# PB_Conn.net
KiCad netlist of a schematic drawn in Altium Designer
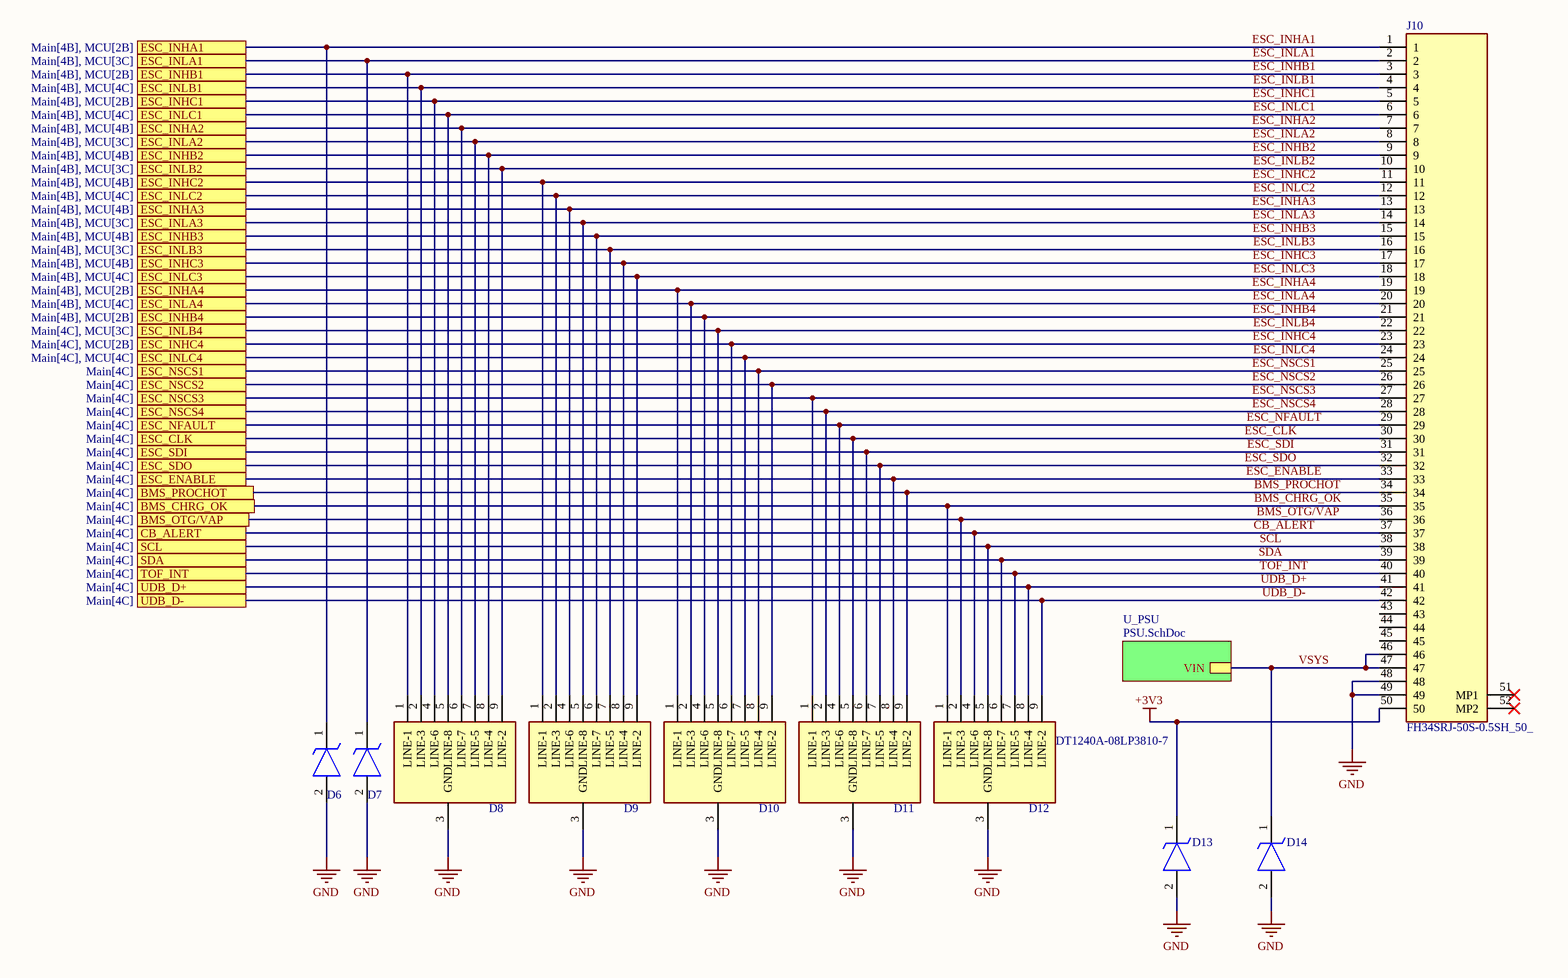
[diagram p0: PB_Conn.SchDoc]

(export (version "E")
  (design (tool "Eeschema 10.0.6"))
  (components
    (comp (ref "D6")
      (value "D1213A-01LP4-7B")
      (footprint "SamacSys:D1213A01LP47B")
      (description "TVS Diode (Uni-directional)")
      (fields (field (name "MOUSER PART NUMBER") "621-D1213A-01LP4-7B"))
      (libsource (lib "*") (part "D1213A-01LP4-7B"))
    )
    (comp (ref "D7")
      (value "D1213A-01LP4-7B")
      (footprint "SamacSys:D1213A01LP47B")
      (description "TVS Diode (Uni-directional)")
      (fields (field (name "MOUSER PART NUMBER") "621-D1213A-01LP4-7B"))
      (libsource (lib "*") (part "D1213A-01LP4-7B"))
    )
    (comp (ref "D8")
      (value "DT1240A-08LP3810-7")
      (footprint "SamacSys:DT1240A08LP38107")
      (description "TVS Diode (Uni-directional)")
      (fields (field (name "MOUSER PART NUMBER") "621-DT1240A08LP38107"))
      (libsource (lib "SamacSys") (part "DT1240A-08LP3810-7"))
    )
    (comp (ref "D9")
      (value "DT1240A-08LP3810-7")
      (footprint "SamacSys:DT1240A08LP38107")
      (description "TVS Diode (Uni-directional)")
      (fields (field (name "MOUSER PART NUMBER") "621-DT1240A08LP38107"))
      (libsource (lib "SamacSys") (part "DT1240A-08LP3810-7"))
    )
    (comp (ref "D10")
      (value "DT1240A-08LP3810-7")
      (footprint "SamacSys:DT1240A08LP38107")
      (description "TVS Diode (Uni-directional)")
      (fields (field (name "MOUSER PART NUMBER") "621-DT1240A08LP38107"))
      (libsource (lib "SamacSys") (part "DT1240A-08LP3810-7"))
    )
    (comp (ref "D11")
      (value "DT1240A-08LP3810-7")
      (footprint "SamacSys:DT1240A08LP38107")
      (description "TVS Diode (Uni-directional)")
      (fields (field (name "MOUSER PART NUMBER") "621-DT1240A08LP38107"))
      (libsource (lib "SamacSys") (part "DT1240A-08LP3810-7"))
    )
    (comp (ref "D12")
      (value "DT1240A-08LP3810-7")
      (footprint "SamacSys:DT1240A08LP38107")
      (description "TVS Diode (Uni-directional)")
      (fields (field (name "MOUSER PART NUMBER") "621-DT1240A08LP38107"))
      (libsource (lib "SamacSys") (part "DT1240A-08LP3810-7"))
    )
    (comp (ref "D13")
      (value "DF2S24FS,L3M")
      (footprint "SamacSys:SODFL1006X45N")
      (description "TVS Diode (Uni-directional)")
      (fields (field (name "MOUSER PART NUMBER") "757-DF2S24FSL3M"))
      (libsource (lib "*") (part "DF2S24FS,L3M"))
    )
    (comp (ref "D14")
      (value "DF2S24FS,L3M")
      (footprint "SamacSys:SODFL1006X45N")
      (description "TVS Diode (Uni-directional)")
      (fields (field (name "MOUSER PART NUMBER") "757-DF2S24FSL3M"))
      (libsource (lib "*") (part "DF2S24FS,L3M"))
    )
    (comp (ref "J10")
      (value "FH34SRJ-50S-0.5SH_50_")
      (footprint "SamacSys:FH34SRJ50S05SH50")
      (description "Connector")
      (fields
        (field (name "MANUFACTURER_PART_NUMBER") "FH34SRJ-50S-0.5SH(50)")
        (field (name "MOUSER PART NUMBER") "798-FH34SRJ50S05SH50")
      )
      (libsource (lib "*") (part "FH34SRJ-50S-0.5SH_50_"))
    )
  )
  (nets
    (net (code "1") (name "+3V3") (class "Default")
      (node (ref "D13") (pin "1") (pinfunction "K_1") (pintype "passive"))
      (node (ref "J10") (pin "50") (pinfunction "50_50") (pintype "passive"))
    )
    (net (code "2") (name "/BMS_CHRG_OK") (class "Default")
      (node (ref "D12") (pin "1") (pinfunction "LINE-1_1") (pintype "passive"))
      (node (ref "J10") (pin "35") (pinfunction "35_35") (pintype "passive"))
    )
    (net (code "3") (name "/BMS_OTG{slash}VAP") (class "Default")
      (node (ref "D12") (pin "2") (pinfunction "LINE-3_2") (pintype "passive"))
      (node (ref "J10") (pin "36") (pinfunction "36_36") (pintype "passive"))
    )
    (net (code "4") (name "/BMS_PROCHOT") (class "Default")
      (node (ref "D11") (pin "9") (pinfunction "LINE-2_9") (pintype "passive"))
      (node (ref "J10") (pin "34") (pinfunction "34_34") (pintype "passive"))
    )
    (net (code "5") (name "/CB_ALERT") (class "Default")
      (node (ref "D12") (pin "4") (pinfunction "LINE-6_4") (pintype "passive"))
      (node (ref "J10") (pin "37") (pinfunction "37_37") (pintype "passive"))
    )
    (net (code "6") (name "/ESC_CLK") (class "Default")
      (node (ref "D11") (pin "5") (pinfunction "LINE-8_5") (pintype "passive"))
      (node (ref "J10") (pin "30") (pinfunction "30_30") (pintype "passive"))
    )
    (net (code "7") (name "/ESC_ENABLE") (class "Default")
      (node (ref "D11") (pin "8") (pinfunction "LINE-4_8") (pintype "passive"))
      (node (ref "J10") (pin "33") (pinfunction "33_33") (pintype "passive"))
    )
    (net (code "8") (name "/ESC_INHA1") (class "Default")
      (node (ref "D6") (pin "1") (pinfunction "K_1") (pintype "passive"))
      (node (ref "J10") (pin "1") (pinfunction "1_1") (pintype "passive"))
    )
    (net (code "9") (name "/ESC_INHA2") (class "Default")
      (node (ref "D8") (pin "6") (pinfunction "LINE-7_6") (pintype "passive"))
      (node (ref "J10") (pin "7") (pinfunction "7_7") (pintype "passive"))
    )
    (net (code "10") (name "/ESC_INHA3") (class "Default")
      (node (ref "D9") (pin "4") (pinfunction "LINE-6_4") (pintype "passive"))
      (node (ref "J10") (pin "13") (pinfunction "13_13") (pintype "passive"))
    )
    (net (code "11") (name "/ESC_INHA4") (class "Default")
      (node (ref "D10") (pin "1") (pinfunction "LINE-1_1") (pintype "passive"))
      (node (ref "J10") (pin "19") (pinfunction "19_19") (pintype "passive"))
    )
    (net (code "12") (name "/ESC_INHB1") (class "Default")
      (node (ref "D8") (pin "1") (pinfunction "LINE-1_1") (pintype "passive"))
      (node (ref "J10") (pin "3") (pinfunction "3_3") (pintype "passive"))
    )
    (net (code "13") (name "/ESC_INHB2") (class "Default")
      (node (ref "D8") (pin "8") (pinfunction "LINE-4_8") (pintype "passive"))
      (node (ref "J10") (pin "9") (pinfunction "9_9") (pintype "passive"))
    )
    (net (code "14") (name "/ESC_INHB3") (class "Default")
      (node (ref "D9") (pin "6") (pinfunction "LINE-7_6") (pintype "passive"))
      (node (ref "J10") (pin "15") (pinfunction "15_15") (pintype "passive"))
    )
    (net (code "15") (name "/ESC_INHB4") (class "Default")
      (node (ref "D10") (pin "4") (pinfunction "LINE-6_4") (pintype "passive"))
      (node (ref "J10") (pin "21") (pinfunction "21_21") (pintype "passive"))
    )
    (net (code "16") (name "/ESC_INHC1") (class "Default")
      (node (ref "D8") (pin "4") (pinfunction "LINE-6_4") (pintype "passive"))
      (node (ref "J10") (pin "5") (pinfunction "5_5") (pintype "passive"))
    )
    (net (code "17") (name "/ESC_INHC2") (class "Default")
      (node (ref "D9") (pin "1") (pinfunction "LINE-1_1") (pintype "passive"))
      (node (ref "J10") (pin "11") (pinfunction "11_11") (pintype "passive"))
    )
    (net (code "18") (name "/ESC_INHC3") (class "Default")
      (node (ref "D9") (pin "8") (pinfunction "LINE-4_8") (pintype "passive"))
      (node (ref "J10") (pin "17") (pinfunction "17_17") (pintype "passive"))
    )
    (net (code "19") (name "/ESC_INHC4") (class "Default")
      (node (ref "D10") (pin "6") (pinfunction "LINE-7_6") (pintype "passive"))
      (node (ref "J10") (pin "23") (pinfunction "23_23") (pintype "passive"))
    )
    (net (code "20") (name "/ESC_INLA1") (class "Default")
      (node (ref "D7") (pin "1") (pinfunction "K_1") (pintype "passive"))
      (node (ref "J10") (pin "2") (pinfunction "2_2") (pintype "passive"))
    )
    (net (code "21") (name "/ESC_INLA2") (class "Default")
      (node (ref "D8") (pin "7") (pinfunction "LINE-5_7") (pintype "passive"))
      (node (ref "J10") (pin "8") (pinfunction "8_8") (pintype "passive"))
    )
    (net (code "22") (name "/ESC_INLA3") (class "Default")
      (node (ref "D9") (pin "5") (pinfunction "LINE-8_5") (pintype "passive"))
      (node (ref "J10") (pin "14") (pinfunction "14_14") (pintype "passive"))
    )
    (net (code "23") (name "/ESC_INLA4") (class "Default")
      (node (ref "D10") (pin "2") (pinfunction "LINE-3_2") (pintype "passive"))
      (node (ref "J10") (pin "20") (pinfunction "20_20") (pintype "passive"))
    )
    (net (code "24") (name "/ESC_INLB1") (class "Default")
      (node (ref "D8") (pin "2") (pinfunction "LINE-3_2") (pintype "passive"))
      (node (ref "J10") (pin "4") (pinfunction "4_4") (pintype "passive"))
    )
    (net (code "25") (name "/ESC_INLB2") (class "Default")
      (node (ref "D8") (pin "9") (pinfunction "LINE-2_9") (pintype "passive"))
      (node (ref "J10") (pin "10") (pinfunction "10_10") (pintype "passive"))
    )
    (net (code "26") (name "/ESC_INLB3") (class "Default")
      (node (ref "D9") (pin "7") (pinfunction "LINE-5_7") (pintype "passive"))
      (node (ref "J10") (pin "16") (pinfunction "16_16") (pintype "passive"))
    )
    (net (code "27") (name "/ESC_INLB4") (class "Default")
      (node (ref "D10") (pin "5") (pinfunction "LINE-8_5") (pintype "passive"))
      (node (ref "J10") (pin "22") (pinfunction "22_22") (pintype "passive"))
    )
    (net (code "28") (name "/ESC_INLC1") (class "Default")
      (node (ref "D8") (pin "5") (pinfunction "LINE-8_5") (pintype "passive"))
      (node (ref "J10") (pin "6") (pinfunction "6_6") (pintype "passive"))
    )
    (net (code "29") (name "/ESC_INLC2") (class "Default")
      (node (ref "D9") (pin "2") (pinfunction "LINE-3_2") (pintype "passive"))
      (node (ref "J10") (pin "12") (pinfunction "12_12") (pintype "passive"))
    )
    (net (code "30") (name "/ESC_INLC3") (class "Default")
      (node (ref "D9") (pin "9") (pinfunction "LINE-2_9") (pintype "passive"))
      (node (ref "J10") (pin "18") (pinfunction "18_18") (pintype "passive"))
    )
    (net (code "31") (name "/ESC_INLC4") (class "Default")
      (node (ref "D10") (pin "7") (pinfunction "LINE-5_7") (pintype "passive"))
      (node (ref "J10") (pin "24") (pinfunction "24_24") (pintype "passive"))
    )
    (net (code "32") (name "/ESC_NFAULT") (class "Default")
      (node (ref "D11") (pin "4") (pinfunction "LINE-6_4") (pintype "passive"))
      (node (ref "J10") (pin "29") (pinfunction "29_29") (pintype "passive"))
    )
    (net (code "33") (name "/ESC_NSCS1") (class "Default")
      (node (ref "D10") (pin "8") (pinfunction "LINE-4_8") (pintype "passive"))
      (node (ref "J10") (pin "25") (pinfunction "25_25") (pintype "passive"))
    )
    (net (code "34") (name "/ESC_NSCS2") (class "Default")
      (node (ref "D10") (pin "9") (pinfunction "LINE-2_9") (pintype "passive"))
      (node (ref "J10") (pin "26") (pinfunction "26_26") (pintype "passive"))
    )
    (net (code "35") (name "/ESC_NSCS3") (class "Default")
      (node (ref "D11") (pin "1") (pinfunction "LINE-1_1") (pintype "passive"))
      (node (ref "J10") (pin "27") (pinfunction "27_27") (pintype "passive"))
    )
    (net (code "36") (name "/ESC_NSCS4") (class "Default")
      (node (ref "D11") (pin "2") (pinfunction "LINE-3_2") (pintype "passive"))
      (node (ref "J10") (pin "28") (pinfunction "28_28") (pintype "passive"))
    )
    (net (code "37") (name "/ESC_SDI") (class "Default")
      (node (ref "D11") (pin "6") (pinfunction "LINE-7_6") (pintype "passive"))
      (node (ref "J10") (pin "31") (pinfunction "31_31") (pintype "passive"))
    )
    (net (code "38") (name "/ESC_SDO") (class "Default")
      (node (ref "D11") (pin "7") (pinfunction "LINE-5_7") (pintype "passive"))
      (node (ref "J10") (pin "32") (pinfunction "32_32") (pintype "passive"))
    )
    (net (code "39") (name "/SCL") (class "Default")
      (node (ref "D12") (pin "5") (pinfunction "LINE-8_5") (pintype "passive"))
      (node (ref "J10") (pin "38") (pinfunction "38_38") (pintype "passive"))
    )
    (net (code "40") (name "/SDA") (class "Default")
      (node (ref "D12") (pin "6") (pinfunction "LINE-7_6") (pintype "passive"))
      (node (ref "J10") (pin "39") (pinfunction "39_39") (pintype "passive"))
    )
    (net (code "41") (name "/TOF_INT") (class "Default")
      (node (ref "D12") (pin "7") (pinfunction "LINE-5_7") (pintype "passive"))
      (node (ref "J10") (pin "40") (pinfunction "40_40") (pintype "passive"))
    )
    (net (code "42") (name "/UDB_D+") (class "Default")
      (node (ref "D12") (pin "8") (pinfunction "LINE-4_8") (pintype "passive"))
      (node (ref "J10") (pin "41") (pinfunction "41_41") (pintype "passive"))
    )
    (net (code "43") (name "/UDB_D-") (class "Default")
      (node (ref "D12") (pin "9") (pinfunction "LINE-2_9") (pintype "passive"))
      (node (ref "J10") (pin "42") (pinfunction "42_42") (pintype "passive"))
    )
    (net (code "44") (name "/VSYS") (class "Default")
      (node (ref "D14") (pin "1") (pinfunction "K_1") (pintype "passive"))
      (node (ref "J10") (pin "46") (pinfunction "46_46") (pintype "passive"))
      (node (ref "J10") (pin "47") (pinfunction "47_47") (pintype "passive"))
    )
    (net (code "45") (name "GND") (class "Default")
      (node (ref "D10") (pin "3") (pinfunction "GND_3") (pintype "passive"))
      (node (ref "D11") (pin "3") (pinfunction "GND_3") (pintype "passive"))
      (node (ref "D12") (pin "3") (pinfunction "GND_3") (pintype "passive"))
      (node (ref "D13") (pin "2") (pinfunction "A_2") (pintype "passive"))
      (node (ref "D14") (pin "2") (pinfunction "A_2") (pintype "passive"))
      (node (ref "D6") (pin "2") (pinfunction "A_2") (pintype "passive"))
      (node (ref "D7") (pin "2") (pinfunction "A_2") (pintype "passive"))
      (node (ref "D8") (pin "3") (pinfunction "GND_3") (pintype "passive"))
      (node (ref "D9") (pin "3") (pinfunction "GND_3") (pintype "passive"))
      (node (ref "J10") (pin "48") (pinfunction "48_48") (pintype "passive"))
      (node (ref "J10") (pin "49") (pinfunction "49_49") (pintype "passive"))
    )
    (net (code "46") (name "unconnected-(J10-MP1-Pad51)") (class "Default")
      (node (ref "J10") (pin "51") (pinfunction "MP1_51") (pintype "passive+no_connect"))
    )
    (net (code "47") (name "unconnected-(J10-MP2-Pad52)") (class "Default")
      (node (ref "J10") (pin "52") (pinfunction "MP2_52") (pintype "passive+no_connect"))
    )
    (net (code "48") (name "unconnected-(J10-Pad43)") (class "Default")
      (node (ref "J10") (pin "43") (pinfunction "43_43") (pintype "passive"))
    )
    (net (code "49") (name "unconnected-(J10-Pad44)") (class "Default")
      (node (ref "J10") (pin "44") (pinfunction "44_44") (pintype "passive"))
    )
    (net (code "50") (name "unconnected-(J10-Pad45)") (class "Default")
      (node (ref "J10") (pin "45") (pinfunction "45_45") (pintype "passive"))
    )
  )
)
